# Ver_5_IR.net
KiCad netlist of a schematic drawn in EAGLE
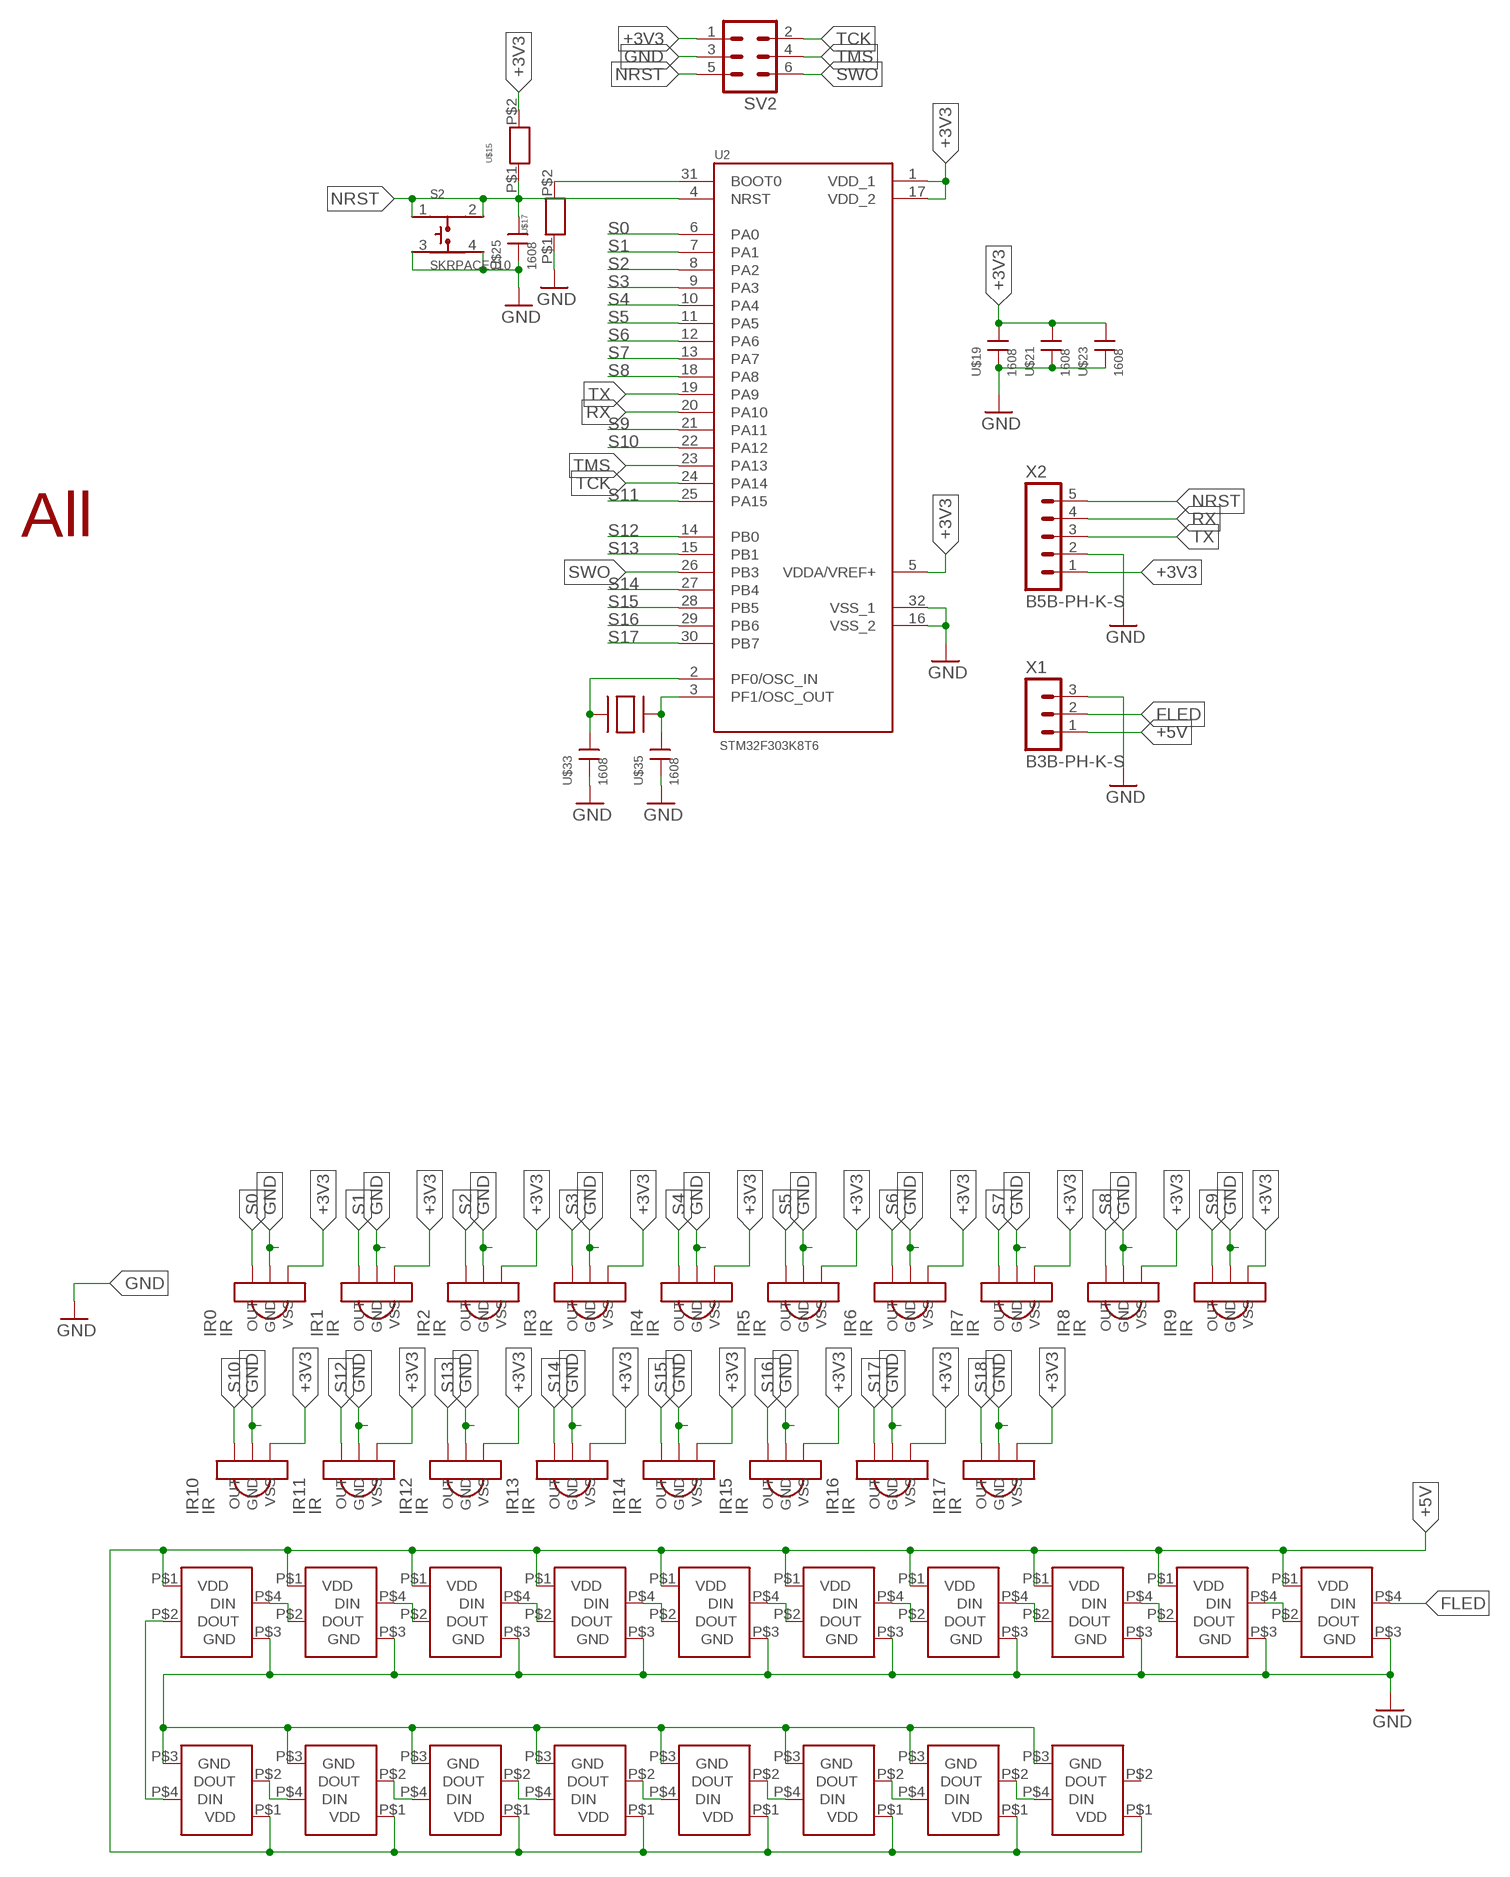
[diagram p0: schematic, sheet 1]

(export (version "E")
  (design (tool "Eeschema 10.0.6"))
  (components
    (comp (ref "F0")
      (value "LED")
      (footprint "eagle-import:LED")
      (libsource (lib "eagle-import") (part "LED"))
    )
    (comp (ref "F1")
      (value "LED")
      (footprint "eagle-import:LED")
      (libsource (lib "eagle-import") (part "LED"))
    )
    (comp (ref "F2")
      (value "LED")
      (footprint "eagle-import:LED")
      (libsource (lib "eagle-import") (part "LED"))
    )
    (comp (ref "F3")
      (value "LED")
      (footprint "eagle-import:LED")
      (libsource (lib "eagle-import") (part "LED"))
    )
    (comp (ref "F4")
      (value "LED")
      (footprint "eagle-import:LED")
      (libsource (lib "eagle-import") (part "LED"))
    )
    (comp (ref "F5")
      (value "LED")
      (footprint "eagle-import:LED")
      (libsource (lib "eagle-import") (part "LED"))
    )
    (comp (ref "F6")
      (value "LED")
      (footprint "eagle-import:LED")
      (libsource (lib "eagle-import") (part "LED"))
    )
    (comp (ref "F7")
      (value "LED")
      (footprint "eagle-import:LED")
      (libsource (lib "eagle-import") (part "LED"))
    )
    (comp (ref "F8")
      (value "LED")
      (footprint "eagle-import:LED")
      (libsource (lib "eagle-import") (part "LED"))
    )
    (comp (ref "F9")
      (value "LED")
      (footprint "eagle-import:LED")
      (libsource (lib "eagle-import") (part "LED"))
    )
    (comp (ref "F10")
      (value "LED")
      (footprint "eagle-import:LED")
      (libsource (lib "eagle-import") (part "LED"))
    )
    (comp (ref "F11")
      (value "LED")
      (footprint "eagle-import:LED")
      (libsource (lib "eagle-import") (part "LED"))
    )
    (comp (ref "F12")
      (value "LED")
      (footprint "eagle-import:LED")
      (libsource (lib "eagle-import") (part "LED"))
    )
    (comp (ref "F13")
      (value "LED")
      (footprint "eagle-import:LED")
      (libsource (lib "eagle-import") (part "LED"))
    )
    (comp (ref "F14")
      (value "LED")
      (footprint "eagle-import:LED")
      (libsource (lib "eagle-import") (part "LED"))
    )
    (comp (ref "F15")
      (value "LED")
      (footprint "eagle-import:LED")
      (libsource (lib "eagle-import") (part "LED"))
    )
    (comp (ref "F16")
      (value "LED")
      (footprint "eagle-import:LED")
      (libsource (lib "eagle-import") (part "LED"))
    )
    (comp (ref "F17")
      (value "LED")
      (footprint "eagle-import:LED")
      (libsource (lib "eagle-import") (part "LED"))
    )
    (comp (ref "IR0") (value "IR") (footprint "eagle-import:IR") (libsource (lib "eagle-import") (part "IR")))
    (comp (ref "IR1") (value "IR") (footprint "eagle-import:IR") (libsource (lib "eagle-import") (part "IR")))
    (comp (ref "IR2") (value "IR") (footprint "eagle-import:IR") (libsource (lib "eagle-import") (part "IR")))
    (comp (ref "IR3") (value "IR") (footprint "eagle-import:IR") (libsource (lib "eagle-import") (part "IR")))
    (comp (ref "IR4") (value "IR") (footprint "eagle-import:IR") (libsource (lib "eagle-import") (part "IR")))
    (comp (ref "IR5") (value "IR") (footprint "eagle-import:IR") (libsource (lib "eagle-import") (part "IR")))
    (comp (ref "IR6") (value "IR") (footprint "eagle-import:IR") (libsource (lib "eagle-import") (part "IR")))
    (comp (ref "IR7") (value "IR") (footprint "eagle-import:IR") (libsource (lib "eagle-import") (part "IR")))
    (comp (ref "IR8") (value "IR") (footprint "eagle-import:IR") (libsource (lib "eagle-import") (part "IR")))
    (comp (ref "IR9") (value "IR") (footprint "eagle-import:IR") (libsource (lib "eagle-import") (part "IR")))
    (comp (ref "IR10")
      (value "IR")
      (footprint "eagle-import:IR")
      (libsource (lib "eagle-import") (part "IR"))
    )
    (comp (ref "IR11")
      (value "IR")
      (footprint "eagle-import:IR")
      (libsource (lib "eagle-import") (part "IR"))
    )
    (comp (ref "IR12")
      (value "IR")
      (footprint "eagle-import:IR")
      (libsource (lib "eagle-import") (part "IR"))
    )
    (comp (ref "IR13")
      (value "IR")
      (footprint "eagle-import:IR")
      (libsource (lib "eagle-import") (part "IR"))
    )
    (comp (ref "IR14")
      (value "IR")
      (footprint "eagle-import:IR")
      (libsource (lib "eagle-import") (part "IR"))
    )
    (comp (ref "IR15")
      (value "IR")
      (footprint "eagle-import:IR")
      (libsource (lib "eagle-import") (part "IR"))
    )
    (comp (ref "IR16")
      (value "IR")
      (footprint "eagle-import:IR")
      (libsource (lib "eagle-import") (part "IR"))
    )
    (comp (ref "IR17")
      (value "IR")
      (footprint "eagle-import:IR")
      (libsource (lib "eagle-import") (part "IR"))
    )
    (comp (ref "S2")
      (value "SKRPACE010")
      (footprint "eagle-import:SW_SKRPACE010")
      (fields (field (name "MF") "ALPS"))
      (libsource (lib "eagle-import") (part "SKRPACE010"))
    )
    (comp (ref "SV2")
      (value "ML6")
      (footprint "eagle-import:ML6")
      (libsource (lib "eagle-import") (part "ML6"))
    )
    (comp (ref "U$1")
      (value "ALL")
      (footprint "eagle-import:ALL")
      (libsource (lib "eagle-import") (part "ALL"))
    )
    (comp (ref "U$15")
      (value "R")
      (footprint "eagle-import:1608")
      (libsource (lib "eagle-import") (part "R"))
    )
    (comp (ref "U$17")
      (value "R")
      (footprint "eagle-import:1608")
      (libsource (lib "eagle-import") (part "R"))
    )
    (comp (ref "U$19")
      (value "1608")
      (footprint "eagle-import:CON")
      (libsource (lib "eagle-import") (part "1608"))
    )
    (comp (ref "U$21")
      (value "1608")
      (footprint "eagle-import:CON")
      (libsource (lib "eagle-import") (part "1608"))
    )
    (comp (ref "U$23")
      (value "1608")
      (footprint "eagle-import:CON")
      (libsource (lib "eagle-import") (part "1608"))
    )
    (comp (ref "U$25")
      (value "1608")
      (footprint "eagle-import:CON")
      (libsource (lib "eagle-import") (part "1608"))
    )
    (comp (ref "U$27")
      (value "SUISYOU")
      (footprint "eagle-import:水晶")
      (libsource (lib "eagle-import") (part "SUISYOU"))
    )
    (comp (ref "U$33")
      (value "1608")
      (footprint "eagle-import:CON")
      (libsource (lib "eagle-import") (part "1608"))
    )
    (comp (ref "U$35")
      (value "1608")
      (footprint "eagle-import:CON")
      (libsource (lib "eagle-import") (part "1608"))
    )
    (comp (ref "U2")
      (value "STM32F303K8T6")
      (footprint "eagle-import:QFP80P900X900X160-32N")
      (fields (field (name "MF") "STMicroelectronics"))
      (libsource (lib "eagle-import") (part "STM32F303K8T6"))
    )
    (comp (ref "X1")
      (value "B3B-PH-K-S")
      (footprint "eagle-import:B3B-PH-K-S")
      (libsource (lib "eagle-import") (part "B3B-PH-K-S"))
    )
    (comp (ref "X2")
      (value "B5B-PH-K-S")
      (footprint "eagle-import:B5B-PH-K-S")
      (libsource (lib "eagle-import") (part "B5B-PH-K-S"))
    )
  )
  (nets
    (net (code "1") (name "+3V3") (class "Default")
      (node (ref "IR0") (pin "P$3") (pinfunction "VSS_P$3") (pintype "bidirectional"))
      (node (ref "IR1") (pin "P$3") (pinfunction "VSS_P$3") (pintype "bidirectional"))
      (node (ref "IR10") (pin "P$3") (pinfunction "VSS_P$3") (pintype "bidirectional"))
      (node (ref "IR11") (pin "P$3") (pinfunction "VSS_P$3") (pintype "bidirectional"))
      (node (ref "IR12") (pin "P$3") (pinfunction "VSS_P$3") (pintype "bidirectional"))
      (node (ref "IR13") (pin "P$3") (pinfunction "VSS_P$3") (pintype "bidirectional"))
      (node (ref "IR14") (pin "P$3") (pinfunction "VSS_P$3") (pintype "bidirectional"))
      (node (ref "IR15") (pin "P$3") (pinfunction "VSS_P$3") (pintype "bidirectional"))
      (node (ref "IR16") (pin "P$3") (pinfunction "VSS_P$3") (pintype "bidirectional"))
      (node (ref "IR17") (pin "P$3") (pinfunction "VSS_P$3") (pintype "bidirectional"))
      (node (ref "IR2") (pin "P$3") (pinfunction "VSS_P$3") (pintype "bidirectional"))
      (node (ref "IR3") (pin "P$3") (pinfunction "VSS_P$3") (pintype "bidirectional"))
      (node (ref "IR4") (pin "P$3") (pinfunction "VSS_P$3") (pintype "bidirectional"))
      (node (ref "IR5") (pin "P$3") (pinfunction "VSS_P$3") (pintype "bidirectional"))
      (node (ref "IR6") (pin "P$3") (pinfunction "VSS_P$3") (pintype "bidirectional"))
      (node (ref "IR7") (pin "P$3") (pinfunction "VSS_P$3") (pintype "bidirectional"))
      (node (ref "IR8") (pin "P$3") (pinfunction "VSS_P$3") (pintype "bidirectional"))
      (node (ref "IR9") (pin "P$3") (pinfunction "VSS_P$3") (pintype "bidirectional"))
      (node (ref "SV2") (pin "1") (pinfunction "1_1") (pintype "passive"))
      (node (ref "U$15") (pin "P$2") (pinfunction "P$2_P$2") (pintype "bidirectional"))
      (node (ref "U$19") (pin "P$1") (pinfunction "1_P$1") (pintype "bidirectional"))
      (node (ref "U$21") (pin "P$1") (pinfunction "1_P$1") (pintype "bidirectional"))
      (node (ref "U$23") (pin "P$1") (pinfunction "1_P$1") (pintype "bidirectional"))
      (node (ref "U2") (pin "1") (pinfunction "VDD_1_1") (pintype "power_in"))
      (node (ref "U2") (pin "17") (pinfunction "VDD_2_17") (pintype "power_in"))
      (node (ref "U2") (pin "5") (pinfunction "VDDA/VREF+_5") (pintype "power_in"))
      (node (ref "X2") (pin "1") (pinfunction "1_1") (pintype "passive"))
    )
    (net (code "2") (name "+5V") (class "Default")
      (node (ref "F0") (pin "P$1") (pinfunction "VDD_P$1") (pintype "bidirectional"))
      (node (ref "F1") (pin "P$1") (pinfunction "VDD_P$1") (pintype "bidirectional"))
      (node (ref "F10") (pin "P$1") (pinfunction "VDD_P$1") (pintype "bidirectional"))
      (node (ref "F11") (pin "P$1") (pinfunction "VDD_P$1") (pintype "bidirectional"))
      (node (ref "F12") (pin "P$1") (pinfunction "VDD_P$1") (pintype "bidirectional"))
      (node (ref "F13") (pin "P$1") (pinfunction "VDD_P$1") (pintype "bidirectional"))
      (node (ref "F14") (pin "P$1") (pinfunction "VDD_P$1") (pintype "bidirectional"))
      (node (ref "F15") (pin "P$1") (pinfunction "VDD_P$1") (pintype "bidirectional"))
      (node (ref "F16") (pin "P$1") (pinfunction "VDD_P$1") (pintype "bidirectional"))
      (node (ref "F17") (pin "P$1") (pinfunction "VDD_P$1") (pintype "bidirectional"))
      (node (ref "F2") (pin "P$1") (pinfunction "VDD_P$1") (pintype "bidirectional"))
      (node (ref "F3") (pin "P$1") (pinfunction "VDD_P$1") (pintype "bidirectional"))
      (node (ref "F4") (pin "P$1") (pinfunction "VDD_P$1") (pintype "bidirectional"))
      (node (ref "F5") (pin "P$1") (pinfunction "VDD_P$1") (pintype "bidirectional"))
      (node (ref "F6") (pin "P$1") (pinfunction "VDD_P$1") (pintype "bidirectional"))
      (node (ref "F7") (pin "P$1") (pinfunction "VDD_P$1") (pintype "bidirectional"))
      (node (ref "F8") (pin "P$1") (pinfunction "VDD_P$1") (pintype "bidirectional"))
      (node (ref "F9") (pin "P$1") (pinfunction "VDD_P$1") (pintype "bidirectional"))
      (node (ref "X1") (pin "1") (pinfunction "1_1") (pintype "passive"))
    )
    (net (code "3") (name "/S11") (class "Default")
      (node (ref "U2") (pin "25") (pinfunction "PA15_25") (pintype "bidirectional"))
    )
    (net (code "4") (name "FLED") (class "Default")
      (node (ref "F0") (pin "P$4") (pinfunction "DIN_P$4") (pintype "bidirectional"))
      (node (ref "X1") (pin "2") (pinfunction "2_2") (pintype "passive"))
    )
    (net (code "5") (name "GND") (class "Default")
      (node (ref "F0") (pin "P$3") (pinfunction "GND_P$3") (pintype "bidirectional"))
      (node (ref "F1") (pin "P$3") (pinfunction "GND_P$3") (pintype "bidirectional"))
      (node (ref "F10") (pin "P$3") (pinfunction "GND_P$3") (pintype "bidirectional"))
      (node (ref "F11") (pin "P$3") (pinfunction "GND_P$3") (pintype "bidirectional"))
      (node (ref "F12") (pin "P$3") (pinfunction "GND_P$3") (pintype "bidirectional"))
      (node (ref "F13") (pin "P$3") (pinfunction "GND_P$3") (pintype "bidirectional"))
      (node (ref "F14") (pin "P$3") (pinfunction "GND_P$3") (pintype "bidirectional"))
      (node (ref "F15") (pin "P$3") (pinfunction "GND_P$3") (pintype "bidirectional"))
      (node (ref "F16") (pin "P$3") (pinfunction "GND_P$3") (pintype "bidirectional"))
      (node (ref "F17") (pin "P$3") (pinfunction "GND_P$3") (pintype "bidirectional"))
      (node (ref "F2") (pin "P$3") (pinfunction "GND_P$3") (pintype "bidirectional"))
      (node (ref "F3") (pin "P$3") (pinfunction "GND_P$3") (pintype "bidirectional"))
      (node (ref "F4") (pin "P$3") (pinfunction "GND_P$3") (pintype "bidirectional"))
      (node (ref "F5") (pin "P$3") (pinfunction "GND_P$3") (pintype "bidirectional"))
      (node (ref "F6") (pin "P$3") (pinfunction "GND_P$3") (pintype "bidirectional"))
      (node (ref "F7") (pin "P$3") (pinfunction "GND_P$3") (pintype "bidirectional"))
      (node (ref "F8") (pin "P$3") (pinfunction "GND_P$3") (pintype "bidirectional"))
      (node (ref "F9") (pin "P$3") (pinfunction "GND_P$3") (pintype "bidirectional"))
      (node (ref "IR0") (pin "P$2") (pinfunction "GND_P$2") (pintype "bidirectional"))
      (node (ref "IR1") (pin "P$2") (pinfunction "GND_P$2") (pintype "bidirectional"))
      (node (ref "IR10") (pin "P$2") (pinfunction "GND_P$2") (pintype "bidirectional"))
      (node (ref "IR11") (pin "P$2") (pinfunction "GND_P$2") (pintype "bidirectional"))
      (node (ref "IR12") (pin "P$2") (pinfunction "GND_P$2") (pintype "bidirectional"))
      (node (ref "IR13") (pin "P$2") (pinfunction "GND_P$2") (pintype "bidirectional"))
      (node (ref "IR14") (pin "P$2") (pinfunction "GND_P$2") (pintype "bidirectional"))
      (node (ref "IR15") (pin "P$2") (pinfunction "GND_P$2") (pintype "bidirectional"))
      (node (ref "IR16") (pin "P$2") (pinfunction "GND_P$2") (pintype "bidirectional"))
      (node (ref "IR17") (pin "P$2") (pinfunction "GND_P$2") (pintype "bidirectional"))
      (node (ref "IR2") (pin "P$2") (pinfunction "GND_P$2") (pintype "bidirectional"))
      (node (ref "IR3") (pin "P$2") (pinfunction "GND_P$2") (pintype "bidirectional"))
      (node (ref "IR4") (pin "P$2") (pinfunction "GND_P$2") (pintype "bidirectional"))
      (node (ref "IR5") (pin "P$2") (pinfunction "GND_P$2") (pintype "bidirectional"))
      (node (ref "IR6") (pin "P$2") (pinfunction "GND_P$2") (pintype "bidirectional"))
      (node (ref "IR7") (pin "P$2") (pinfunction "GND_P$2") (pintype "bidirectional"))
      (node (ref "IR8") (pin "P$2") (pinfunction "GND_P$2") (pintype "bidirectional"))
      (node (ref "IR9") (pin "P$2") (pinfunction "GND_P$2") (pintype "bidirectional"))
      (node (ref "S2") (pin "3") (pinfunction "3_3") (pintype "bidirectional"))
      (node (ref "S2") (pin "4") (pinfunction "4_4") (pintype "bidirectional"))
      (node (ref "SV2") (pin "3") (pinfunction "3_3") (pintype "passive"))
      (node (ref "U$17") (pin "P$1") (pinfunction "P$1_P$1") (pintype "bidirectional"))
      (node (ref "U$19") (pin "P$2") (pinfunction "2_P$2") (pintype "bidirectional"))
      (node (ref "U$21") (pin "P$2") (pinfunction "2_P$2") (pintype "bidirectional"))
      (node (ref "U$23") (pin "P$2") (pinfunction "2_P$2") (pintype "bidirectional"))
      (node (ref "U$25") (pin "P$2") (pinfunction "2_P$2") (pintype "bidirectional"))
      (node (ref "U$33") (pin "P$2") (pinfunction "2_P$2") (pintype "bidirectional"))
      (node (ref "U$35") (pin "P$2") (pinfunction "2_P$2") (pintype "bidirectional"))
      (node (ref "U2") (pin "16") (pinfunction "VSS_2_16") (pintype "power_in"))
      (node (ref "U2") (pin "32") (pinfunction "VSS_1_32") (pintype "power_in"))
      (node (ref "X1") (pin "3") (pinfunction "3_3") (pintype "passive"))
      (node (ref "X2") (pin "2") (pinfunction "2_2") (pintype "passive"))
    )
    (net (code "6") (name "NRST") (class "Default")
      (node (ref "S2") (pin "1") (pinfunction "1_1") (pintype "bidirectional"))
      (node (ref "S2") (pin "2") (pinfunction "2_2") (pintype "bidirectional"))
      (node (ref "SV2") (pin "5") (pinfunction "5_5") (pintype "passive"))
      (node (ref "U$15") (pin "P$1") (pinfunction "P$1_P$1") (pintype "bidirectional"))
      (node (ref "U$25") (pin "P$1") (pinfunction "1_P$1") (pintype "bidirectional"))
      (node (ref "U2") (pin "4") (pinfunction "NRST_4") (pintype "bidirectional"))
      (node (ref "X2") (pin "5") (pinfunction "5_5") (pintype "passive"))
    )
    (net (code "7") (name "Net-(F0-DOUT)") (class "Default")
      (node (ref "F0") (pin "P$2") (pinfunction "DOUT_P$2") (pintype "bidirectional"))
      (node (ref "F1") (pin "P$4") (pinfunction "DIN_P$4") (pintype "bidirectional"))
    )
    (net (code "8") (name "Net-(F1-DOUT)") (class "Default")
      (node (ref "F1") (pin "P$2") (pinfunction "DOUT_P$2") (pintype "bidirectional"))
      (node (ref "F2") (pin "P$4") (pinfunction "DIN_P$4") (pintype "bidirectional"))
    )
    (net (code "9") (name "Net-(F2-DOUT)") (class "Default")
      (node (ref "F2") (pin "P$2") (pinfunction "DOUT_P$2") (pintype "bidirectional"))
      (node (ref "F3") (pin "P$4") (pinfunction "DIN_P$4") (pintype "bidirectional"))
    )
    (net (code "10") (name "Net-(F3-DOUT)") (class "Default")
      (node (ref "F3") (pin "P$2") (pinfunction "DOUT_P$2") (pintype "bidirectional"))
      (node (ref "F4") (pin "P$4") (pinfunction "DIN_P$4") (pintype "bidirectional"))
    )
    (net (code "11") (name "Net-(F4-DOUT)") (class "Default")
      (node (ref "F4") (pin "P$2") (pinfunction "DOUT_P$2") (pintype "bidirectional"))
      (node (ref "F5") (pin "P$4") (pinfunction "DIN_P$4") (pintype "bidirectional"))
    )
    (net (code "12") (name "Net-(F5-DOUT)") (class "Default")
      (node (ref "F5") (pin "P$2") (pinfunction "DOUT_P$2") (pintype "bidirectional"))
      (node (ref "F6") (pin "P$4") (pinfunction "DIN_P$4") (pintype "bidirectional"))
    )
    (net (code "13") (name "Net-(F6-DOUT)") (class "Default")
      (node (ref "F6") (pin "P$2") (pinfunction "DOUT_P$2") (pintype "bidirectional"))
      (node (ref "F7") (pin "P$4") (pinfunction "DIN_P$4") (pintype "bidirectional"))
    )
    (net (code "14") (name "Net-(F7-DOUT)") (class "Default")
      (node (ref "F7") (pin "P$2") (pinfunction "DOUT_P$2") (pintype "bidirectional"))
      (node (ref "F8") (pin "P$4") (pinfunction "DIN_P$4") (pintype "bidirectional"))
    )
    (net (code "15") (name "Net-(F8-DOUT)") (class "Default")
      (node (ref "F8") (pin "P$2") (pinfunction "DOUT_P$2") (pintype "bidirectional"))
      (node (ref "F9") (pin "P$4") (pinfunction "DIN_P$4") (pintype "bidirectional"))
    )
    (net (code "16") (name "Net-(F10-DIN)") (class "Default")
      (node (ref "F10") (pin "P$4") (pinfunction "DIN_P$4") (pintype "bidirectional"))
      (node (ref "F9") (pin "P$2") (pinfunction "DOUT_P$2") (pintype "bidirectional"))
    )
    (net (code "17") (name "Net-(F10-DOUT)") (class "Default")
      (node (ref "F10") (pin "P$2") (pinfunction "DOUT_P$2") (pintype "bidirectional"))
      (node (ref "F11") (pin "P$4") (pinfunction "DIN_P$4") (pintype "bidirectional"))
    )
    (net (code "18") (name "Net-(F11-DOUT)") (class "Default")
      (node (ref "F11") (pin "P$2") (pinfunction "DOUT_P$2") (pintype "bidirectional"))
      (node (ref "F12") (pin "P$4") (pinfunction "DIN_P$4") (pintype "bidirectional"))
    )
    (net (code "19") (name "Net-(F12-DOUT)") (class "Default")
      (node (ref "F12") (pin "P$2") (pinfunction "DOUT_P$2") (pintype "bidirectional"))
      (node (ref "F13") (pin "P$4") (pinfunction "DIN_P$4") (pintype "bidirectional"))
    )
    (net (code "20") (name "Net-(F13-DOUT)") (class "Default")
      (node (ref "F13") (pin "P$2") (pinfunction "DOUT_P$2") (pintype "bidirectional"))
      (node (ref "F14") (pin "P$4") (pinfunction "DIN_P$4") (pintype "bidirectional"))
    )
    (net (code "21") (name "Net-(F14-DOUT)") (class "Default")
      (node (ref "F14") (pin "P$2") (pinfunction "DOUT_P$2") (pintype "bidirectional"))
      (node (ref "F15") (pin "P$4") (pinfunction "DIN_P$4") (pintype "bidirectional"))
    )
    (net (code "22") (name "Net-(F15-DOUT)") (class "Default")
      (node (ref "F15") (pin "P$2") (pinfunction "DOUT_P$2") (pintype "bidirectional"))
      (node (ref "F16") (pin "P$4") (pinfunction "DIN_P$4") (pintype "bidirectional"))
    )
    (net (code "23") (name "Net-(F16-DOUT)") (class "Default")
      (node (ref "F16") (pin "P$2") (pinfunction "DOUT_P$2") (pintype "bidirectional"))
      (node (ref "F17") (pin "P$4") (pinfunction "DIN_P$4") (pintype "bidirectional"))
    )
    (net (code "24") (name "Net-(U$33-1)") (class "Default")
      (node (ref "U$27") (pin "P$1") (pinfunction "P$1_P$1") (pintype "bidirectional"))
      (node (ref "U$33") (pin "P$1") (pinfunction "1_P$1") (pintype "bidirectional"))
      (node (ref "U2") (pin "2") (pinfunction "PF0/OSC_IN_2") (pintype "bidirectional"))
    )
    (net (code "25") (name "Net-(U$35-1)") (class "Default")
      (node (ref "U$27") (pin "P$2") (pinfunction "P$2_P$2") (pintype "bidirectional"))
      (node (ref "U$35") (pin "P$1") (pinfunction "1_P$1") (pintype "bidirectional"))
      (node (ref "U2") (pin "3") (pinfunction "PF1/OSC_OUT_3") (pintype "bidirectional"))
    )
    (net (code "26") (name "Net-(U2-BOOT0)") (class "Default")
      (node (ref "U$17") (pin "P$2") (pinfunction "P$2_P$2") (pintype "bidirectional"))
      (node (ref "U2") (pin "31") (pinfunction "BOOT0_31") (pintype "input"))
    )
    (net (code "27") (name "RX") (class "Default")
      (node (ref "U2") (pin "20") (pinfunction "PA10_20") (pintype "bidirectional"))
      (node (ref "X2") (pin "4") (pinfunction "4_4") (pintype "passive"))
    )
    (net (code "28") (name "S0") (class "Default")
      (node (ref "IR0") (pin "P$1") (pinfunction "OUT_P$1") (pintype "bidirectional"))
      (node (ref "U2") (pin "6") (pinfunction "PA0_6") (pintype "bidirectional"))
    )
    (net (code "29") (name "S1") (class "Default")
      (node (ref "IR1") (pin "P$1") (pinfunction "OUT_P$1") (pintype "bidirectional"))
      (node (ref "U2") (pin "7") (pinfunction "PA1_7") (pintype "bidirectional"))
    )
    (net (code "30") (name "S2") (class "Default")
      (node (ref "IR2") (pin "P$1") (pinfunction "OUT_P$1") (pintype "bidirectional"))
      (node (ref "U2") (pin "8") (pinfunction "PA2_8") (pintype "bidirectional"))
    )
    (net (code "31") (name "S3") (class "Default")
      (node (ref "IR3") (pin "P$1") (pinfunction "OUT_P$1") (pintype "bidirectional"))
      (node (ref "U2") (pin "9") (pinfunction "PA3_9") (pintype "bidirectional"))
    )
    (net (code "32") (name "S4") (class "Default")
      (node (ref "IR4") (pin "P$1") (pinfunction "OUT_P$1") (pintype "bidirectional"))
      (node (ref "U2") (pin "10") (pinfunction "PA4_10") (pintype "bidirectional"))
    )
    (net (code "33") (name "S5") (class "Default")
      (node (ref "IR5") (pin "P$1") (pinfunction "OUT_P$1") (pintype "bidirectional"))
      (node (ref "U2") (pin "11") (pinfunction "PA5_11") (pintype "bidirectional"))
    )
    (net (code "34") (name "S6") (class "Default")
      (node (ref "IR6") (pin "P$1") (pinfunction "OUT_P$1") (pintype "bidirectional"))
      (node (ref "U2") (pin "12") (pinfunction "PA6_12") (pintype "bidirectional"))
    )
    (net (code "35") (name "S7") (class "Default")
      (node (ref "IR7") (pin "P$1") (pinfunction "OUT_P$1") (pintype "bidirectional"))
      (node (ref "U2") (pin "13") (pinfunction "PA7_13") (pintype "bidirectional"))
    )
    (net (code "36") (name "S8") (class "Default")
      (node (ref "IR8") (pin "P$1") (pinfunction "OUT_P$1") (pintype "bidirectional"))
      (node (ref "U2") (pin "18") (pinfunction "PA8_18") (pintype "bidirectional"))
    )
    (net (code "37") (name "S9") (class "Default")
      (node (ref "IR9") (pin "P$1") (pinfunction "OUT_P$1") (pintype "bidirectional"))
      (node (ref "U2") (pin "21") (pinfunction "PA11_21") (pintype "bidirectional"))
    )
    (net (code "38") (name "S10") (class "Default")
      (node (ref "IR10") (pin "P$1") (pinfunction "OUT_P$1") (pintype "bidirectional"))
      (node (ref "U2") (pin "22") (pinfunction "PA12_22") (pintype "bidirectional"))
    )
    (net (code "39") (name "S12") (class "Default")
      (node (ref "IR11") (pin "P$1") (pinfunction "OUT_P$1") (pintype "bidirectional"))
      (node (ref "U2") (pin "14") (pinfunction "PB0_14") (pintype "bidirectional"))
    )
    (net (code "40") (name "S13") (class "Default")
      (node (ref "IR12") (pin "P$1") (pinfunction "OUT_P$1") (pintype "bidirectional"))
      (node (ref "U2") (pin "15") (pinfunction "PB1_15") (pintype "bidirectional"))
    )
    (net (code "41") (name "S14") (class "Default")
      (node (ref "IR13") (pin "P$1") (pinfunction "OUT_P$1") (pintype "bidirectional"))
      (node (ref "U2") (pin "27") (pinfunction "PB4_27") (pintype "bidirectional"))
    )
    (net (code "42") (name "S15") (class "Default")
      (node (ref "IR14") (pin "P$1") (pinfunction "OUT_P$1") (pintype "bidirectional"))
      (node (ref "U2") (pin "28") (pinfunction "PB5_28") (pintype "bidirectional"))
    )
    (net (code "43") (name "S16") (class "Default")
      (node (ref "IR15") (pin "P$1") (pinfunction "OUT_P$1") (pintype "bidirectional"))
      (node (ref "U2") (pin "29") (pinfunction "PB6_29") (pintype "bidirectional"))
    )
    (net (code "44") (name "S17") (class "Default")
      (node (ref "IR16") (pin "P$1") (pinfunction "OUT_P$1") (pintype "bidirectional"))
      (node (ref "U2") (pin "30") (pinfunction "PB7_30") (pintype "bidirectional"))
    )
    (net (code "45") (name "S18") (class "Default")
      (node (ref "IR17") (pin "P$1") (pinfunction "OUT_P$1") (pintype "bidirectional"))
    )
    (net (code "46") (name "SWO") (class "Default")
      (node (ref "SV2") (pin "6") (pinfunction "6_6") (pintype "passive"))
      (node (ref "U2") (pin "26") (pinfunction "PB3_26") (pintype "bidirectional"))
    )
    (net (code "47") (name "TCK") (class "Default")
      (node (ref "SV2") (pin "2") (pinfunction "2_2") (pintype "passive"))
      (node (ref "U2") (pin "24") (pinfunction "PA14_24") (pintype "bidirectional"))
    )
    (net (code "48") (name "TMS") (class "Default")
      (node (ref "SV2") (pin "4") (pinfunction "4_4") (pintype "passive"))
      (node (ref "U2") (pin "23") (pinfunction "PA13_23") (pintype "bidirectional"))
    )
    (net (code "49") (name "TX") (class "Default")
      (node (ref "U2") (pin "19") (pinfunction "PA9_19") (pintype "bidirectional"))
      (node (ref "X2") (pin "3") (pinfunction "3_3") (pintype "passive"))
    )
    (net (code "50") (name "unconnected-(F17-DOUT-PadP$2)") (class "Default")
      (node (ref "F17") (pin "P$2") (pinfunction "DOUT_P$2") (pintype "bidirectional"))
    )
  )
)
